# io-ol2.net
KiCad netlist of a schematic drawn in EAGLE
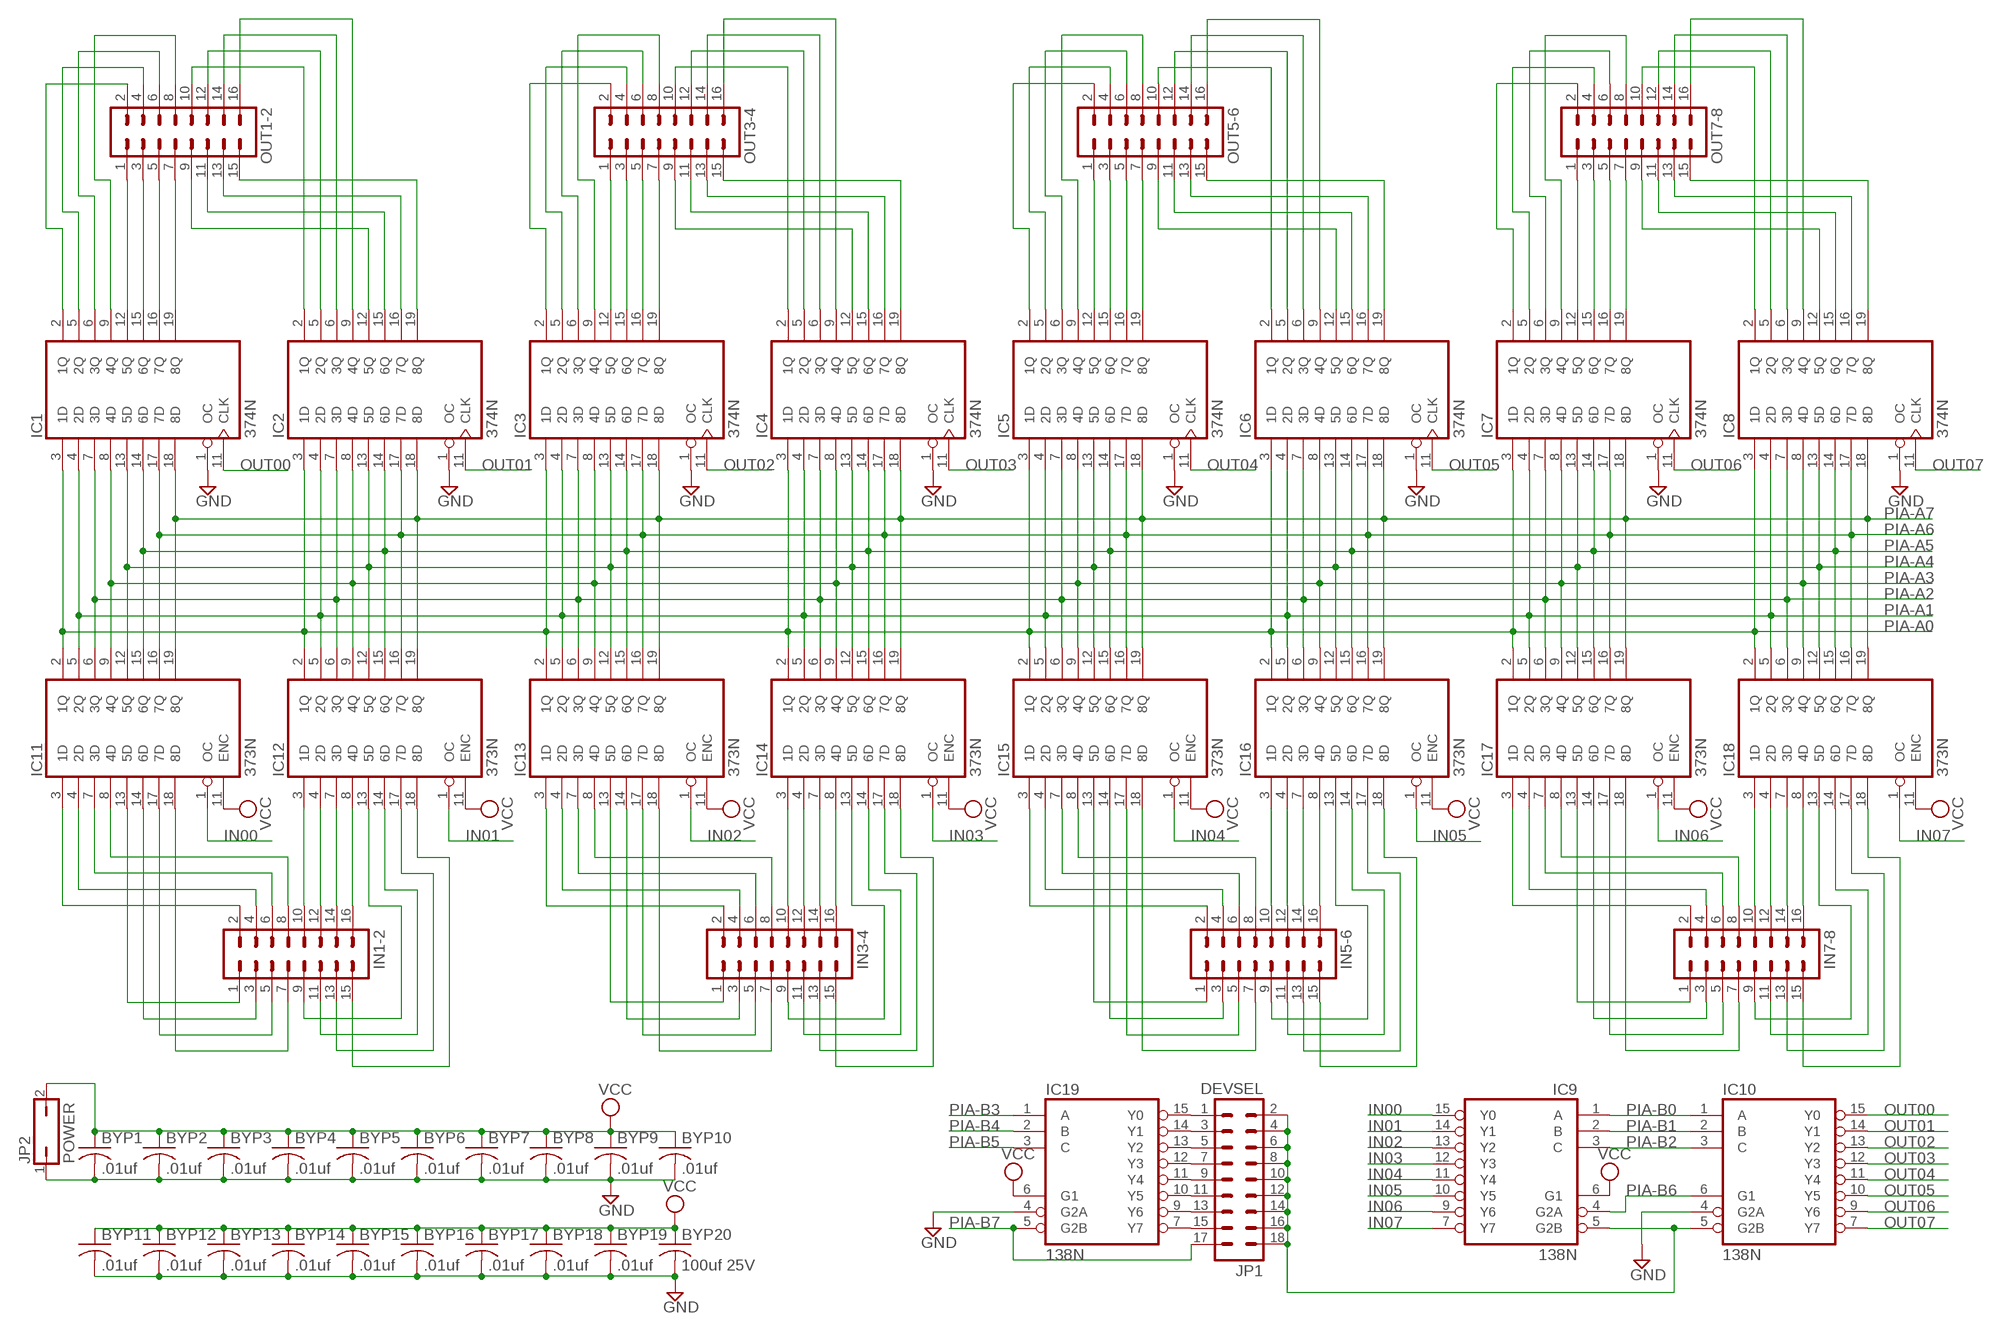
[diagram p0: schematic, sheet 1]
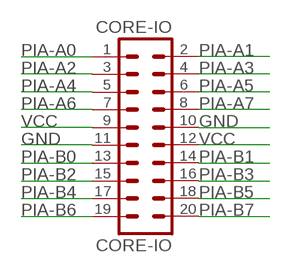
[diagram p1: schematic, sheet 2]

(export (version "E")
  (design (tool "Eeschema 10.0.6"))
  (components
    (comp (ref "BYP1")
      (value ".01uf")
      (footprint "eagle-import:C050-025X075")
      (libsource (lib "eagle-import") (part "C-US050-025X075"))
    )
    (comp (ref "BYP2")
      (value ".01uf")
      (footprint "eagle-import:C050-025X075")
      (libsource (lib "eagle-import") (part "C-US050-025X075"))
    )
    (comp (ref "BYP3")
      (value ".01uf")
      (footprint "eagle-import:C050-025X075")
      (libsource (lib "eagle-import") (part "C-US050-025X075"))
    )
    (comp (ref "BYP4")
      (value ".01uf")
      (footprint "eagle-import:C050-025X075")
      (libsource (lib "eagle-import") (part "C-US050-025X075"))
    )
    (comp (ref "BYP5")
      (value ".01uf")
      (footprint "eagle-import:C050-025X075")
      (libsource (lib "eagle-import") (part "C-US050-025X075"))
    )
    (comp (ref "BYP6")
      (value ".01uf")
      (footprint "eagle-import:C050-025X075")
      (libsource (lib "eagle-import") (part "C-US050-025X075"))
    )
    (comp (ref "BYP7")
      (value ".01uf")
      (footprint "eagle-import:C050-025X075")
      (libsource (lib "eagle-import") (part "C-US050-025X075"))
    )
    (comp (ref "BYP8")
      (value ".01uf")
      (footprint "eagle-import:C050-025X075")
      (libsource (lib "eagle-import") (part "C-US050-025X075"))
    )
    (comp (ref "BYP9")
      (value ".01uf")
      (footprint "eagle-import:C050-025X075")
      (libsource (lib "eagle-import") (part "C-US050-025X075"))
    )
    (comp (ref "BYP10")
      (value ".01uf")
      (footprint "eagle-import:C050-025X075")
      (libsource (lib "eagle-import") (part "C-US050-025X075"))
    )
    (comp (ref "BYP11")
      (value ".01uf")
      (footprint "eagle-import:C050-025X075")
      (libsource (lib "eagle-import") (part "C-US050-025X075"))
    )
    (comp (ref "BYP12")
      (value ".01uf")
      (footprint "eagle-import:C050-025X075")
      (libsource (lib "eagle-import") (part "C-US050-025X075"))
    )
    (comp (ref "BYP13")
      (value ".01uf")
      (footprint "eagle-import:C050-025X075")
      (libsource (lib "eagle-import") (part "C-US050-025X075"))
    )
    (comp (ref "BYP14")
      (value ".01uf")
      (footprint "eagle-import:C050-025X075")
      (libsource (lib "eagle-import") (part "C-US050-025X075"))
    )
    (comp (ref "BYP15")
      (value ".01uf")
      (footprint "eagle-import:C050-025X075")
      (libsource (lib "eagle-import") (part "C-US050-025X075"))
    )
    (comp (ref "BYP16")
      (value ".01uf")
      (footprint "eagle-import:C050-025X075")
      (libsource (lib "eagle-import") (part "C-US050-025X075"))
    )
    (comp (ref "BYP17")
      (value ".01uf")
      (footprint "eagle-import:C050-025X075")
      (libsource (lib "eagle-import") (part "C-US050-025X075"))
    )
    (comp (ref "BYP18")
      (value ".01uf")
      (footprint "eagle-import:C050-025X075")
      (libsource (lib "eagle-import") (part "C-US050-025X075"))
    )
    (comp (ref "BYP19")
      (value ".01uf")
      (footprint "eagle-import:C050-025X075")
      (libsource (lib "eagle-import") (part "C-US050-025X075"))
    )
    (comp (ref "BYP20")
      (value "100uf 25V")
      (footprint "eagle-import:C150-064X183")
      (libsource (lib "eagle-import") (part "C-US150-064X183"))
    )
    (comp (ref "IC1")
      (value "374N")
      (footprint "eagle-import:DIL20")
      (libsource (lib "eagle-import") (part "74374NLS"))
    )
    (comp (ref "IC2")
      (value "374N")
      (footprint "eagle-import:DIL20")
      (libsource (lib "eagle-import") (part "74374NLS"))
    )
    (comp (ref "IC3")
      (value "374N")
      (footprint "eagle-import:DIL20")
      (libsource (lib "eagle-import") (part "74374NLS"))
    )
    (comp (ref "IC4")
      (value "374N")
      (footprint "eagle-import:DIL20")
      (libsource (lib "eagle-import") (part "74374NLS"))
    )
    (comp (ref "IC5")
      (value "374N")
      (footprint "eagle-import:DIL20")
      (libsource (lib "eagle-import") (part "74374NLS"))
    )
    (comp (ref "IC6")
      (value "374N")
      (footprint "eagle-import:DIL20")
      (libsource (lib "eagle-import") (part "74374NLS"))
    )
    (comp (ref "IC7")
      (value "374N")
      (footprint "eagle-import:DIL20")
      (libsource (lib "eagle-import") (part "74374NLS"))
    )
    (comp (ref "IC8")
      (value "374N")
      (footprint "eagle-import:DIL20")
      (libsource (lib "eagle-import") (part "74374NLS"))
    )
    (comp (ref "IC9")
      (value "138N")
      (footprint "eagle-import:DIL16")
      (libsource (lib "eagle-import") (part "74138NLS"))
    )
    (comp (ref "IC10")
      (value "138N")
      (footprint "eagle-import:DIL16")
      (libsource (lib "eagle-import") (part "74138NLS"))
    )
    (comp (ref "IC11")
      (value "373N")
      (footprint "eagle-import:DIL20")
      (libsource (lib "eagle-import") (part "74373NLS"))
    )
    (comp (ref "IC12")
      (value "373N")
      (footprint "eagle-import:DIL20")
      (libsource (lib "eagle-import") (part "74373NLS"))
    )
    (comp (ref "IC13")
      (value "373N")
      (footprint "eagle-import:DIL20")
      (libsource (lib "eagle-import") (part "74373NLS"))
    )
    (comp (ref "IC14")
      (value "373N")
      (footprint "eagle-import:DIL20")
      (libsource (lib "eagle-import") (part "74373NLS"))
    )
    (comp (ref "IC15")
      (value "373N")
      (footprint "eagle-import:DIL20")
      (libsource (lib "eagle-import") (part "74373NLS"))
    )
    (comp (ref "IC16")
      (value "373N")
      (footprint "eagle-import:DIL20")
      (libsource (lib "eagle-import") (part "74373NLS"))
    )
    (comp (ref "IC17")
      (value "373N")
      (footprint "eagle-import:DIL20")
      (libsource (lib "eagle-import") (part "74373NLS"))
    )
    (comp (ref "IC18")
      (value "373N")
      (footprint "eagle-import:DIL20")
      (libsource (lib "eagle-import") (part "74373NLS"))
    )
    (comp (ref "IC19")
      (value "138N")
      (footprint "eagle-import:DIL16")
      (libsource (lib "eagle-import") (part "74138NLS"))
    )
    (comp (ref "IN1-2")
      (value "MA08-2")
      (footprint "eagle-import:MA08-2")
      (libsource (lib "eagle-import") (part "MA08-2"))
    )
    (comp (ref "IN3-4")
      (value "MA08-2")
      (footprint "eagle-import:MA08-2")
      (libsource (lib "eagle-import") (part "MA08-2"))
    )
    (comp (ref "IN5-6")
      (value "MA08-2")
      (footprint "eagle-import:MA08-2")
      (libsource (lib "eagle-import") (part "MA08-2"))
    )
    (comp (ref "IN7-8")
      (value "MA08-2")
      (footprint "eagle-import:MA08-2")
      (libsource (lib "eagle-import") (part "MA08-2"))
    )
    (comp (ref "JP1")
      (value "DEVSEL")
      (footprint "eagle-import:MA09-2")
      (libsource (lib "eagle-import") (part "MA09-2"))
    )
    (comp (ref "JP2")
      (value "POWER")
      (footprint "eagle-import:JP1")
      (libsource (lib "eagle-import") (part "JP1Q"))
    )
    (comp (ref "OUT1-2")
      (value "MA08-2")
      (footprint "eagle-import:MA08-2")
      (libsource (lib "eagle-import") (part "MA08-2"))
    )
    (comp (ref "OUT3-4")
      (value "MA08-2")
      (footprint "eagle-import:MA08-2")
      (libsource (lib "eagle-import") (part "MA08-2"))
    )
    (comp (ref "OUT5-6")
      (value "MA08-2")
      (footprint "eagle-import:MA08-2")
      (libsource (lib "eagle-import") (part "MA08-2"))
    )
    (comp (ref "OUT7-8")
      (value "MA08-2")
      (footprint "eagle-import:MA08-2")
      (libsource (lib "eagle-import") (part "MA08-2"))
    )
    (comp (ref "CORE-IO")
      (value "CORE-IO")
      (footprint "eagle-import:MA10-2")
      (libsource (lib "eagle-import") (part "MA10-2"))
    )
  )
  (nets
    (net (code "1") (name "GND") (class "Default")
      (node (ref "BYP1") (pin "2") (pinfunction "2_2") (pintype "passive"))
      (node (ref "BYP10") (pin "2") (pinfunction "2_2") (pintype "passive"))
      (node (ref "BYP11") (pin "2") (pinfunction "2_2") (pintype "passive"))
      (node (ref "BYP12") (pin "2") (pinfunction "2_2") (pintype "passive"))
      (node (ref "BYP13") (pin "2") (pinfunction "2_2") (pintype "passive"))
      (node (ref "BYP14") (pin "2") (pinfunction "2_2") (pintype "passive"))
      (node (ref "BYP15") (pin "2") (pinfunction "2_2") (pintype "passive"))
      (node (ref "BYP16") (pin "2") (pinfunction "2_2") (pintype "passive"))
      (node (ref "BYP17") (pin "2") (pinfunction "2_2") (pintype "passive"))
      (node (ref "BYP18") (pin "2") (pinfunction "2_2") (pintype "passive"))
      (node (ref "BYP19") (pin "2") (pinfunction "2_2") (pintype "passive"))
      (node (ref "BYP2") (pin "2") (pinfunction "2_2") (pintype "passive"))
      (node (ref "BYP20") (pin "2") (pinfunction "2_2") (pintype "passive"))
      (node (ref "BYP3") (pin "2") (pinfunction "2_2") (pintype "passive"))
      (node (ref "BYP4") (pin "2") (pinfunction "2_2") (pintype "passive"))
      (node (ref "BYP5") (pin "2") (pinfunction "2_2") (pintype "passive"))
      (node (ref "BYP6") (pin "2") (pinfunction "2_2") (pintype "passive"))
      (node (ref "BYP7") (pin "2") (pinfunction "2_2") (pintype "passive"))
      (node (ref "BYP8") (pin "2") (pinfunction "2_2") (pintype "passive"))
      (node (ref "BYP9") (pin "2") (pinfunction "2_2") (pintype "passive"))
      (node (ref "CORE-IO") (pin "10") (pinfunction "10_10") (pintype "passive"))
      (node (ref "CORE-IO") (pin "11") (pinfunction "11_11") (pintype "passive"))
      (node (ref "IC1") (pin "1") (pinfunction "OC_1") (pintype "input"))
      (node (ref "IC10") (pin "4") (pinfunction "G2A_4") (pintype "input"))
      (node (ref "IC19") (pin "4") (pinfunction "G2A_4") (pintype "input"))
      (node (ref "IC2") (pin "1") (pinfunction "OC_1") (pintype "input"))
      (node (ref "IC3") (pin "1") (pinfunction "OC_1") (pintype "input"))
      (node (ref "IC4") (pin "1") (pinfunction "OC_1") (pintype "input"))
      (node (ref "IC5") (pin "1") (pinfunction "OC_1") (pintype "input"))
      (node (ref "IC6") (pin "1") (pinfunction "OC_1") (pintype "input"))
      (node (ref "IC7") (pin "1") (pinfunction "OC_1") (pintype "input"))
      (node (ref "IC8") (pin "1") (pinfunction "OC_1") (pintype "input"))
      (node (ref "JP2") (pin "1") (pinfunction "1_1") (pintype "passive"))
    )
    (net (code "2") (name "IN00") (class "Default")
      (node (ref "IC11") (pin "1") (pinfunction "OC_1") (pintype "input"))
      (node (ref "IC9") (pin "15") (pinfunction "Y0_15") (pintype "output"))
    )
    (net (code "3") (name "IN01") (class "Default")
      (node (ref "IC12") (pin "1") (pinfunction "OC_1") (pintype "input"))
      (node (ref "IC9") (pin "14") (pinfunction "Y1_14") (pintype "output"))
    )
    (net (code "4") (name "IN02") (class "Default")
      (node (ref "IC13") (pin "1") (pinfunction "OC_1") (pintype "input"))
      (node (ref "IC9") (pin "13") (pinfunction "Y2_13") (pintype "output"))
    )
    (net (code "5") (name "IN03") (class "Default")
      (node (ref "IC14") (pin "1") (pinfunction "OC_1") (pintype "input"))
      (node (ref "IC9") (pin "12") (pinfunction "Y3_12") (pintype "output"))
    )
    (net (code "6") (name "IN04") (class "Default")
      (node (ref "IC15") (pin "1") (pinfunction "OC_1") (pintype "input"))
      (node (ref "IC9") (pin "11") (pinfunction "Y4_11") (pintype "output"))
    )
    (net (code "7") (name "IN05") (class "Default")
      (node (ref "IC16") (pin "1") (pinfunction "OC_1") (pintype "input"))
      (node (ref "IC9") (pin "10") (pinfunction "Y5_10") (pintype "output"))
    )
    (net (code "8") (name "IN06") (class "Default")
      (node (ref "IC17") (pin "1") (pinfunction "OC_1") (pintype "input"))
      (node (ref "IC9") (pin "9") (pinfunction "Y6_9") (pintype "output"))
    )
    (net (code "9") (name "IN07") (class "Default")
      (node (ref "IC18") (pin "1") (pinfunction "OC_1") (pintype "input"))
      (node (ref "IC9") (pin "7") (pinfunction "Y7_7") (pintype "output"))
    )
    (net (code "10") (name "Net-(IC1A-1Q)") (class "Default")
      (node (ref "IC1") (pin "2") (pinfunction "1Q_2") (pintype "tri_state"))
      (node (ref "OUT1-2") (pin "2") (pinfunction "2_2") (pintype "passive"))
    )
    (net (code "11") (name "Net-(IC1A-2Q)") (class "Default")
      (node (ref "IC1") (pin "5") (pinfunction "2Q_5") (pintype "tri_state"))
      (node (ref "OUT1-2") (pin "4") (pinfunction "4_4") (pintype "passive"))
    )
    (net (code "12") (name "Net-(IC1A-3Q)") (class "Default")
      (node (ref "IC1") (pin "6") (pinfunction "3Q_6") (pintype "tri_state"))
      (node (ref "OUT1-2") (pin "6") (pinfunction "6_6") (pintype "passive"))
    )
    (net (code "13") (name "Net-(IC1A-4Q)") (class "Default")
      (node (ref "IC1") (pin "9") (pinfunction "4Q_9") (pintype "tri_state"))
      (node (ref "OUT1-2") (pin "8") (pinfunction "8_8") (pintype "passive"))
    )
    (net (code "14") (name "Net-(IC1A-5Q)") (class "Default")
      (node (ref "IC1") (pin "12") (pinfunction "5Q_12") (pintype "tri_state"))
      (node (ref "OUT1-2") (pin "1") (pinfunction "1_1") (pintype "passive"))
    )
    (net (code "15") (name "Net-(IC1A-6Q)") (class "Default")
      (node (ref "IC1") (pin "15") (pinfunction "6Q_15") (pintype "tri_state"))
      (node (ref "OUT1-2") (pin "3") (pinfunction "3_3") (pintype "passive"))
    )
    (net (code "16") (name "Net-(IC1A-7Q)") (class "Default")
      (node (ref "IC1") (pin "16") (pinfunction "7Q_16") (pintype "tri_state"))
      (node (ref "OUT1-2") (pin "5") (pinfunction "5_5") (pintype "passive"))
    )
    (net (code "17") (name "Net-(IC1A-8Q)") (class "Default")
      (node (ref "IC1") (pin "19") (pinfunction "8Q_19") (pintype "tri_state"))
      (node (ref "OUT1-2") (pin "7") (pinfunction "7_7") (pintype "passive"))
    )
    (net (code "18") (name "Net-(IC2A-1Q)") (class "Default")
      (node (ref "IC2") (pin "2") (pinfunction "1Q_2") (pintype "tri_state"))
      (node (ref "OUT1-2") (pin "10") (pinfunction "10_10") (pintype "passive"))
    )
    (net (code "19") (name "Net-(IC2A-2Q)") (class "Default")
      (node (ref "IC2") (pin "5") (pinfunction "2Q_5") (pintype "tri_state"))
      (node (ref "OUT1-2") (pin "12") (pinfunction "12_12") (pintype "passive"))
    )
    (net (code "20") (name "Net-(IC2A-3Q)") (class "Default")
      (node (ref "IC2") (pin "6") (pinfunction "3Q_6") (pintype "tri_state"))
      (node (ref "OUT1-2") (pin "14") (pinfunction "14_14") (pintype "passive"))
    )
    (net (code "21") (name "Net-(IC2A-4Q)") (class "Default")
      (node (ref "IC2") (pin "9") (pinfunction "4Q_9") (pintype "tri_state"))
      (node (ref "OUT1-2") (pin "16") (pinfunction "16_16") (pintype "passive"))
    )
    (net (code "22") (name "Net-(IC2A-5Q)") (class "Default")
      (node (ref "IC2") (pin "12") (pinfunction "5Q_12") (pintype "tri_state"))
      (node (ref "OUT1-2") (pin "9") (pinfunction "9_9") (pintype "passive"))
    )
    (net (code "23") (name "Net-(IC2A-6Q)") (class "Default")
      (node (ref "IC2") (pin "15") (pinfunction "6Q_15") (pintype "tri_state"))
      (node (ref "OUT1-2") (pin "11") (pinfunction "11_11") (pintype "passive"))
    )
    (net (code "24") (name "Net-(IC2A-7Q)") (class "Default")
      (node (ref "IC2") (pin "16") (pinfunction "7Q_16") (pintype "tri_state"))
      (node (ref "OUT1-2") (pin "13") (pinfunction "13_13") (pintype "passive"))
    )
    (net (code "25") (name "Net-(IC2A-8Q)") (class "Default")
      (node (ref "IC2") (pin "19") (pinfunction "8Q_19") (pintype "tri_state"))
      (node (ref "OUT1-2") (pin "15") (pinfunction "15_15") (pintype "passive"))
    )
    (net (code "26") (name "Net-(IC3A-1Q)") (class "Default")
      (node (ref "IC3") (pin "2") (pinfunction "1Q_2") (pintype "tri_state"))
      (node (ref "OUT3-4") (pin "2") (pinfunction "2_2") (pintype "passive"))
    )
    (net (code "27") (name "Net-(IC3A-2Q)") (class "Default")
      (node (ref "IC3") (pin "5") (pinfunction "2Q_5") (pintype "tri_state"))
      (node (ref "OUT3-4") (pin "4") (pinfunction "4_4") (pintype "passive"))
    )
    (net (code "28") (name "Net-(IC3A-3Q)") (class "Default")
      (node (ref "IC3") (pin "6") (pinfunction "3Q_6") (pintype "tri_state"))
      (node (ref "OUT3-4") (pin "6") (pinfunction "6_6") (pintype "passive"))
    )
    (net (code "29") (name "Net-(IC3A-4Q)") (class "Default")
      (node (ref "IC3") (pin "9") (pinfunction "4Q_9") (pintype "tri_state"))
      (node (ref "OUT3-4") (pin "8") (pinfunction "8_8") (pintype "passive"))
    )
    (net (code "30") (name "Net-(IC3A-5Q)") (class "Default")
      (node (ref "IC3") (pin "12") (pinfunction "5Q_12") (pintype "tri_state"))
      (node (ref "OUT3-4") (pin "1") (pinfunction "1_1") (pintype "passive"))
    )
    (net (code "31") (name "Net-(IC3A-6Q)") (class "Default")
      (node (ref "IC3") (pin "15") (pinfunction "6Q_15") (pintype "tri_state"))
      (node (ref "OUT3-4") (pin "3") (pinfunction "3_3") (pintype "passive"))
    )
    (net (code "32") (name "Net-(IC3A-7Q)") (class "Default")
      (node (ref "IC3") (pin "16") (pinfunction "7Q_16") (pintype "tri_state"))
      (node (ref "OUT3-4") (pin "5") (pinfunction "5_5") (pintype "passive"))
    )
    (net (code "33") (name "Net-(IC3A-8Q)") (class "Default")
      (node (ref "IC3") (pin "19") (pinfunction "8Q_19") (pintype "tri_state"))
      (node (ref "OUT3-4") (pin "7") (pinfunction "7_7") (pintype "passive"))
    )
    (net (code "34") (name "Net-(IC4A-1Q)") (class "Default")
      (node (ref "IC4") (pin "2") (pinfunction "1Q_2") (pintype "tri_state"))
      (node (ref "OUT3-4") (pin "10") (pinfunction "10_10") (pintype "passive"))
    )
    (net (code "35") (name "Net-(IC4A-2Q)") (class "Default")
      (node (ref "IC4") (pin "5") (pinfunction "2Q_5") (pintype "tri_state"))
      (node (ref "OUT3-4") (pin "12") (pinfunction "12_12") (pintype "passive"))
    )
    (net (code "36") (name "Net-(IC4A-3Q)") (class "Default")
      (node (ref "IC4") (pin "6") (pinfunction "3Q_6") (pintype "tri_state"))
      (node (ref "OUT3-4") (pin "14") (pinfunction "14_14") (pintype "passive"))
    )
    (net (code "37") (name "Net-(IC4A-4Q)") (class "Default")
      (node (ref "IC4") (pin "9") (pinfunction "4Q_9") (pintype "tri_state"))
      (node (ref "OUT3-4") (pin "16") (pinfunction "16_16") (pintype "passive"))
    )
    (net (code "38") (name "Net-(IC4A-5Q)") (class "Default")
      (node (ref "IC4") (pin "12") (pinfunction "5Q_12") (pintype "tri_state"))
      (node (ref "OUT3-4") (pin "9") (pinfunction "9_9") (pintype "passive"))
    )
    (net (code "39") (name "Net-(IC4A-6Q)") (class "Default")
      (node (ref "IC4") (pin "15") (pinfunction "6Q_15") (pintype "tri_state"))
      (node (ref "OUT3-4") (pin "11") (pinfunction "11_11") (pintype "passive"))
    )
    (net (code "40") (name "Net-(IC4A-7Q)") (class "Default")
      (node (ref "IC4") (pin "16") (pinfunction "7Q_16") (pintype "tri_state"))
      (node (ref "OUT3-4") (pin "13") (pinfunction "13_13") (pintype "passive"))
    )
    (net (code "41") (name "Net-(IC4A-8Q)") (class "Default")
      (node (ref "IC4") (pin "19") (pinfunction "8Q_19") (pintype "tri_state"))
      (node (ref "OUT3-4") (pin "15") (pinfunction "15_15") (pintype "passive"))
    )
    (net (code "42") (name "Net-(IC5A-1Q)") (class "Default")
      (node (ref "IC5") (pin "2") (pinfunction "1Q_2") (pintype "tri_state"))
      (node (ref "OUT5-6") (pin "2") (pinfunction "2_2") (pintype "passive"))
    )
    (net (code "43") (name "Net-(IC5A-2Q)") (class "Default")
      (node (ref "IC5") (pin "5") (pinfunction "2Q_5") (pintype "tri_state"))
      (node (ref "OUT5-6") (pin "4") (pinfunction "4_4") (pintype "passive"))
    )
    (net (code "44") (name "Net-(IC5A-3Q)") (class "Default")
      (node (ref "IC5") (pin "6") (pinfunction "3Q_6") (pintype "tri_state"))
      (node (ref "OUT5-6") (pin "6") (pinfunction "6_6") (pintype "passive"))
    )
    (net (code "45") (name "Net-(IC5A-4Q)") (class "Default")
      (node (ref "IC5") (pin "9") (pinfunction "4Q_9") (pintype "tri_state"))
      (node (ref "OUT5-6") (pin "8") (pinfunction "8_8") (pintype "passive"))
    )
    (net (code "46") (name "Net-(IC5A-5Q)") (class "Default")
      (node (ref "IC5") (pin "12") (pinfunction "5Q_12") (pintype "tri_state"))
      (node (ref "OUT5-6") (pin "1") (pinfunction "1_1") (pintype "passive"))
    )
    (net (code "47") (name "Net-(IC5A-6Q)") (class "Default")
      (node (ref "IC5") (pin "15") (pinfunction "6Q_15") (pintype "tri_state"))
      (node (ref "OUT5-6") (pin "3") (pinfunction "3_3") (pintype "passive"))
    )
    (net (code "48") (name "Net-(IC5A-7Q)") (class "Default")
      (node (ref "IC5") (pin "16") (pinfunction "7Q_16") (pintype "tri_state"))
      (node (ref "OUT5-6") (pin "5") (pinfunction "5_5") (pintype "passive"))
    )
    (net (code "49") (name "Net-(IC5A-8Q)") (class "Default")
      (node (ref "IC5") (pin "19") (pinfunction "8Q_19") (pintype "tri_state"))
      (node (ref "OUT5-6") (pin "7") (pinfunction "7_7") (pintype "passive"))
    )
    (net (code "50") (name "Net-(IC6A-1Q)") (class "Default")
      (node (ref "IC6") (pin "2") (pinfunction "1Q_2") (pintype "tri_state"))
      (node (ref "OUT5-6") (pin "10") (pinfunction "10_10") (pintype "passive"))
    )
    (net (code "51") (name "Net-(IC6A-2Q)") (class "Default")
      (node (ref "IC6") (pin "5") (pinfunction "2Q_5") (pintype "tri_state"))
      (node (ref "OUT5-6") (pin "12") (pinfunction "12_12") (pintype "passive"))
    )
    (net (code "52") (name "Net-(IC6A-3Q)") (class "Default")
      (node (ref "IC6") (pin "6") (pinfunction "3Q_6") (pintype "tri_state"))
      (node (ref "OUT5-6") (pin "14") (pinfunction "14_14") (pintype "passive"))
    )
    (net (code "53") (name "Net-(IC6A-4Q)") (class "Default")
      (node (ref "IC6") (pin "9") (pinfunction "4Q_9") (pintype "tri_state"))
      (node (ref "OUT5-6") (pin "16") (pinfunction "16_16") (pintype "passive"))
    )
    (net (code "54") (name "Net-(IC6A-5Q)") (class "Default")
      (node (ref "IC6") (pin "12") (pinfunction "5Q_12") (pintype "tri_state"))
      (node (ref "OUT5-6") (pin "9") (pinfunction "9_9") (pintype "passive"))
    )
    (net (code "55") (name "Net-(IC6A-6Q)") (class "Default")
      (node (ref "IC6") (pin "15") (pinfunction "6Q_15") (pintype "tri_state"))
      (node (ref "OUT5-6") (pin "11") (pinfunction "11_11") (pintype "passive"))
    )
    (net (code "56") (name "Net-(IC6A-7Q)") (class "Default")
      (node (ref "IC6") (pin "16") (pinfunction "7Q_16") (pintype "tri_state"))
      (node (ref "OUT5-6") (pin "13") (pinfunction "13_13") (pintype "passive"))
    )
    (net (code "57") (name "Net-(IC6A-8Q)") (class "Default")
      (node (ref "IC6") (pin "19") (pinfunction "8Q_19") (pintype "tri_state"))
      (node (ref "OUT5-6") (pin "15") (pinfunction "15_15") (pintype "passive"))
    )
    (net (code "58") (name "Net-(IC7A-1Q)") (class "Default")
      (node (ref "IC7") (pin "2") (pinfunction "1Q_2") (pintype "tri_state"))
      (node (ref "OUT7-8") (pin "2") (pinfunction "2_2") (pintype "passive"))
    )
    (net (code "59") (name "Net-(IC7A-2Q)") (class "Default")
      (node (ref "IC7") (pin "5") (pinfunction "2Q_5") (pintype "tri_state"))
      (node (ref "OUT7-8") (pin "4") (pinfunction "4_4") (pintype "passive"))
    )
    (net (code "60") (name "Net-(IC7A-3Q)") (class "Default")
      (node (ref "IC7") (pin "6") (pinfunction "3Q_6") (pintype "tri_state"))
      (node (ref "OUT7-8") (pin "6") (pinfunction "6_6") (pintype "passive"))
    )
    (net (code "61") (name "Net-(IC7A-4Q)") (class "Default")
      (node (ref "IC7") (pin "9") (pinfunction "4Q_9") (pintype "tri_state"))
      (node (ref "OUT7-8") (pin "8") (pinfunction "8_8") (pintype "passive"))
    )
    (net (code "62") (name "Net-(IC7A-5Q)") (class "Default")
      (node (ref "IC7") (pin "12") (pinfunction "5Q_12") (pintype "tri_state"))
      (node (ref "OUT7-8") (pin "1") (pinfunction "1_1") (pintype "passive"))
    )
    (net (code "63") (name "Net-(IC7A-6Q)") (class "Default")
      (node (ref "IC7") (pin "15") (pinfunction "6Q_15") (pintype "tri_state"))
      (node (ref "OUT7-8") (pin "3") (pinfunction "3_3") (pintype "passive"))
    )
    (net (code "64") (name "Net-(IC7A-7Q)") (class "Default")
      (node (ref "IC7") (pin "16") (pinfunction "7Q_16") (pintype "tri_state"))
      (node (ref "OUT7-8") (pin "5") (pinfunction "5_5") (pintype "passive"))
    )
    (net (code "65") (name "Net-(IC7A-8Q)") (class "Default")
      (node (ref "IC7") (pin "19") (pinfunction "8Q_19") (pintype "tri_state"))
      (node (ref "OUT7-8") (pin "7") (pinfunction "7_7") (pintype "passive"))
    )
    (net (code "66") (name "Net-(IC8A-1Q)") (class "Default")
      (node (ref "IC8") (pin "2") (pinfunction "1Q_2") (pintype "tri_state"))
      (node (ref "OUT7-8") (pin "10") (pinfunction "10_10") (pintype "passive"))
    )
    (net (code "67") (name "Net-(IC8A-2Q)") (class "Default")
      (node (ref "IC8") (pin "5") (pinfunction "2Q_5") (pintype "tri_state"))
      (node (ref "OUT7-8") (pin "12") (pinfunction "12_12") (pintype "passive"))
    )
    (net (code "68") (name "Net-(IC8A-3Q)") (class "Default")
      (node (ref "IC8") (pin "6") (pinfunction "3Q_6") (pintype "tri_state"))
      (node (ref "OUT7-8") (pin "14") (pinfunction "14_14") (pintype "passive"))
    )
    (net (code "69") (name "Net-(IC8A-4Q)") (class "Default")
      (node (ref "IC8") (pin "9") (pinfunction "4Q_9") (pintype "tri_state"))
      (node (ref "OUT7-8") (pin "16") (pinfunction "16_16") (pintype "passive"))
    )
    (net (code "70") (name "Net-(IC8A-5Q)") (class "Default")
      (node (ref "IC8") (pin "12") (pinfunction "5Q_12") (pintype "tri_state"))
      (node (ref "OUT7-8") (pin "9") (pinfunction "9_9") (pintype "passive"))
    )
    (net (code "71") (name "Net-(IC8A-6Q)") (class "Default")
      (node (ref "IC8") (pin "15") (pinfunction "6Q_15") (pintype "tri_state"))
      (node (ref "OUT7-8") (pin "11") (pinfunction "11_11") (pintype "passive"))
    )
    (net (code "72") (name "Net-(IC8A-7Q)") (class "Default")
      (node (ref "IC8") (pin "16") (pinfunction "7Q_16") (pintype "tri_state"))
      (node (ref "OUT7-8") (pin "13") (pinfunction "13_13") (pintype "passive"))
    )
    (net (code "73") (name "Net-(IC8A-8Q)") (class "Default")
      (node (ref "IC8") (pin "19") (pinfunction "8Q_19") (pintype "tri_state"))
      (node (ref "OUT7-8") (pin "15") (pinfunction "15_15") (pintype "passive"))
    )
    (net (code "74") (name "Net-(IC10A-G2B)") (class "Default")
      (node (ref "IC10") (pin "5") (pinfunction "G2B_5") (pintype "input"))
      (node (ref "IC9") (pin "5") (pinfunction "G2B_5") (pintype "input"))
      (node (ref "JP1") (pin "10") (pinfunction "10_10") (pintype "passive"))
      (node (ref "JP1") (pin "12") (pinfunction "12_12") (pintype "passive"))
      (node (ref "JP1") (pin "14") (pinfunction "14_14") (pintype "passive"))
      (node (ref "JP1") (pin "16") (pinfunction "16_16") (pintype "passive"))
      (node (ref "JP1") (pin "18") (pinfunction "18_18") (pintype "passive"))
      (node (ref "JP1") (pin "2") (pinfunction "2_2") (pintype "passive"))
      (node (ref "JP1") (pin "4") (pinfunction "4_4") (pintype "passive"))
      (node (ref "JP1") (pin "6") (pinfunction "6_6") (pintype "passive"))
      (node (ref "JP1") (pin "8") (pinfunction "8_8") (pintype "passive"))
    )
    (net (code "75") (name "Net-(IC11A-1D)") (class "Default")
      (node (ref "IC11") (pin "3") (pinfunction "1D_3") (pintype "input"))
      (node (ref "IN1-2") (pin "2") (pinfunction "2_2") (pintype "passive"))
    )
    (net (code "76") (name "Net-(IC11A-2D)") (class "Default")
      (node (ref "IC11") (pin "4") (pinfunction "2D_4") (pintype "input"))
      (node (ref "IN1-2") (pin "4") (pinfunction "4_4") (pintype "passive"))
    )
    (net (code "77") (name "Net-(IC11A-3D)") (class "Default")
      (node (ref "IC11") (pin "7") (pinfunction "3D_7") (pintype "input"))
      (node (ref "IN1-2") (pin "6") (pinfunction "6_6") (pintype "passive"))
    )
    (net (code "78") (name "Net-(IC11A-4D)") (class "Default")
      (node (ref "IC11") (pin "8") (pinfunction "4D_8") (pintype "input"))
      (node (ref "IN1-2") (pin "8") (pinfunction "8_8") (pintype "passive"))
    )
    (net (code "79") (name "Net-(IC11A-5D)") (class "Default")
      (node (ref "IC11") (pin "13") (pinfunction "5D_13") (pintype "input"))
      (node (ref "IN1-2") (pin "1") (pinfunction "1_1") (pintype "passive"))
    )
    (net (code "80") (name "Net-(IC11A-6D)") (class "Default")
      (node (ref "IC11") (pin "14") (pinfunction "6D_14") (pintype "input"))
      (node (ref "IN1-2") (pin "3") (pinfunction "3_3") (pintype "passive"))
    )
    (net (code "81") (name "Net-(IC11A-7D)") (class "Default")
      (node (ref "IC11") (pin "17") (pinfunction "7D_17") (pintype "input"))
      (node (ref "IN1-2") (pin "5") (pinfunction "5_5") (pintype "passive"))
    )
    (net (code "82") (name "Net-(IC11A-8D)") (class "Default")
      (node (ref "IC11") (pin "18") (pinfunction "8D_18") (pintype "input"))
      (node (ref "IN1-2") (pin "7") (pinfunction "7_7") (pintype "passive"))
    )
    (net (code "83") (name "Net-(IC12A-1D)") (class "Default")
      (node (ref "IC12") (pin "3") (pinfunction "1D_3") (pintype "input"))
      (node (ref "IN1-2") (pin "10") (pinfunction "10_10") (pintype "passive"))
    )
    (net (code "84") (name "Net-(IC12A-2D)") (class "Default")
      (node (ref "IC12") (pin "4") (pinfunction "2D_4") (pintype "input"))
      (node (ref "IN1-2") (pin "12") (pinfunction "12_12") (pintype "passive"))
    )
    (net (code "85") (name "Net-(IC12A-3D)") (class "Default")
      (node (ref "IC12") (pin "7") (pinfunction "3D_7") (pintype "input"))
      (node (ref "IN1-2") (pin "14") (pinfunction "14_14") (pintype "passive"))
    )
    (net (code "86") (name "Net-(IC12A-4D)") (class "Default")
      (node (ref "IC12") (pin "8") (pinfunction "4D_8") (pintype "input"))
      (node (ref "IN1-2") (pin "16") (pinfunction "16_16") (pintype "passive"))
    )
    (net (code "87") (name "Net-(IC12A-5D)") (class "Default")
      (node (ref "IC12") (pin "13") (pinfunction "5D_13") (pintype "input"))
      (node (ref "IN1-2") (pin "9") (pinfunction "9_9") (pintype "passive"))
    )
    (net (code "88") (name "Net-(IC12A-6D)") (class "Default")
      (node (ref "IC12") (pin "14") (pinfunction "6D_14") (pintype "input"))
      (node (ref "IN1-2") (pin "11") (pinfunction "11_11") (pintype "passive"))
    )
    (net (code "89") (name "Net-(IC12A-7D)") (class "Default")
      (node (ref "IC12") (pin "17") (pinfunction "7D_17") (pintype "input"))
      (node (ref "IN1-2") (pin "13") (pinfunction "13_13") (pintype "passive"))
    )
    (net (code "90") (name "Net-(IC12A-8D)") (class "Default")
      (node (ref "IC12") (pin "18") (pinfunction "8D_18") (pintype "input"))
      (node (ref "IN1-2") (pin "15") (pinfunction "15_15") (pintype "passive"))
    )
    (net (code "91") (name "Net-(IC13A-1D)") (class "Default")
      (node (ref "IC13") (pin "3") (pinfunction "1D_3") (pintype "input"))
      (node (ref "IN3-4") (pin "2") (pinfunction "2_2") (pintype "passive"))
    )
    (net (code "92") (name "Net-(IC13A-2D)") (class "Default")
      (node (ref "IC13") (pin "4") (pinfunction "2D_4") (pintype "input"))
      (node (ref "IN3-4") (pin "4") (pinfunction "4_4") (pintype "passive"))
    )
    (net (code "93") (name "Net-(IC13A-3D)") (class "Default")
      (node (ref "IC13") (pin "7") (pinfunction "3D_7") (pintype "input"))
      (node (ref "IN3-4") (pin "6") (pinfunction "6_6") (pintype "passive"))
    )
    (net (code "94") (name "Net-(IC13A-4D)") (class "Default")
      (node (ref "IC13") (pin "8") (pinfunction "4D_8") (pintype "input"))
      (node (ref "IN3-4") (pin "8") (pinfunction "8_8") (pintype "passive"))
    )
    (net (code "95") (name "Net-(IC13A-5D)") (class "Default")
      (node (ref "IC13") (pin "13") (pinfunction "5D_13") (pintype "input"))
      (node (ref "IN3-4") (pin "1") (pinfunction "1_1") (pintype "passive"))
    )
    (net (code "96") (name "Net-(IC13A-6D)") (class "Default")
      (node (ref "IC13") (pin "14") (pinfunction "6D_14") (pintype "input"))
      (node (ref "IN3-4") (pin "3") (pinfunction "3_3") (pintype "passive"))
    )
    (net (code "97") (name "Net-(IC13A-7D)") (class "Default")
      (node (ref "IC13") (pin "17") (pinfunction "7D_17") (pintype "input"))
      (node (ref "IN3-4") (pin "5") (pinfunction "5_5") (pintype "passive"))
    )
    (net (code "98") (name "Net-(IC13A-8D)") (class "Default")
      (node (ref "IC13") (pin "18") (pinfunction "8D_18") (pintype "input"))
      (node (ref "IN3-4") (pin "7") (pinfunction "7_7") (pintype "passive"))
    )
    (net (code "99") (name "Net-(IC14A-1D)") (class "Default")
      (node (ref "IC14") (pin "3") (pinfunction "1D_3") (pintype "input"))
      (node (ref "IN3-4") (pin "10") (pinfunction "10_10") (pintype "passive"))
    )
    (net (code "100") (name "Net-(IC14A-2D)") (class "Default")
      (node (ref "IC14") (pin "4") (pinfunction "2D_4") (pintype "input"))
      (node (ref "IN3-4") (pin "12") (pinfunction "12_12") (pintype "passive"))
    )
    (net (code "101") (name "Net-(IC14A-3D)") (class "Default")
      (node (ref "IC14") (pin "7") (pinfunction "3D_7") (pintype "input"))
      (node (ref "IN3-4") (pin "14") (pinfunction "14_14") (pintype "passive"))
    )
    (net (code "102") (name "Net-(IC14A-4D)") (class "Default")
      (node (ref "IC14") (pin "8") (pinfunction "4D_8") (pintype "input"))
      (node (ref "IN3-4") (pin "16") (pinfunction "16_16") (pintype "passive"))
    )
    (net (code "103") (name "Net-(IC14A-5D)") (class "Default")
      (node (ref "IC14") (pin "13") (pinfunction "5D_13") (pintype "input"))
      (node (ref "IN3-4") (pin "9") (pinfunction "9_9") (pintype "passive"))
    )
    (net (code "104") (name "Net-(IC14A-6D)") (class "Default")
      (node (ref "IC14") (pin "14") (pinfunction "6D_14") (pintype "input"))
      (node (ref "IN3-4") (pin "11") (pinfunction "11_11") (pintype "passive"))
    )
    (net (code "105") (name "Net-(IC14A-7D)") (class "Default")
      (node (ref "IC14") (pin "17") (pinfunction "7D_17") (pintype "input"))
      (node (ref "IN3-4") (pin "13") (pinfunction "13_13") (pintype "passive"))
    )
    (net (code "106") (name "Net-(IC14A-8D)") (class "Default")
      (node (ref "IC14") (pin "18") (pinfunction "8D_18") (pintype "input"))
      (node (ref "IN3-4") (pin "15") (pinfunction "15_15") (pintype "passive"))
    )
    (net (code "107") (name "Net-(IC15A-1D)") (class "Default")
      (node (ref "IC15") (pin "3") (pinfunction "1D_3") (pintype "input"))
      (node (ref "IN5-6") (pin "2") (pinfunction "2_2") (pintype "passive"))
    )
    (net (code "108") (name "Net-(IC15A-2D)") (class "Default")
      (node (ref "IC15") (pin "4") (pinfunction "2D_4") (pintype "input"))
      (node (ref "IN5-6") (pin "4") (pinfunction "4_4") (pintype "passive"))
    )
    (net (code "109") (name "Net-(IC15A-3D)") (class "Default")
      (node (ref "IC15") (pin "7") (pinfunction "3D_7") (pintype "input"))
      (node (ref "IN5-6") (pin "6") (pinfunction "6_6") (pintype "passive"))
    )
    (net (code "110") (name "Net-(IC15A-4D)") (class "Default")
      (node (ref "IC15") (pin "8") (pinfunction "4D_8") (pintype "input"))
      (node (ref "IN5-6") (pin "8") (pinfunction "8_8") (pintype "passive"))
    )
    (net (code "111") (name "Net-(IC15A-5D)") (class "Default")
      (node (ref "IC15") (pin "13") (pinfunction "5D_13") (pintype "input"))
      (node (ref "IN5-6") (pin "1") (pinfunction "1_1") (pintype "passive"))
    )
    (net (code "112") (name "Net-(IC15A-6D)") (class "Default")
      (node (ref "IC15") (pin "14") (pinfunction "6D_14") (pintype "input"))
      (node (ref "IN5-6") (pin "3") (pinfunction "3_3") (pintype "passive"))
    )
    (net (code "113") (name "Net-(IC15A-7D)") (class "Default")
      (node (ref "IC15") (pin "17") (pinfunction "7D_17") (pintype "input"))
      (node (ref "IN5-6") (pin "5") (pinfunction "5_5") (pintype "passive"))
    )
    (net (code "114") (name "Net-(IC15A-8D)") (class "Default")
      (node (ref "IC15") (pin "18") (pinfunction "8D_18") (pintype "input"))
      (node (ref "IN5-6") (pin "7") (pinfunction "7_7") (pintype "passive"))
    )
    (net (code "115") (name "Net-(IC16A-1D)") (class "Default")
      (node (ref "IC16") (pin "3") (pinfunction "1D_3") (pintype "input"))
      (node (ref "IN5-6") (pin "10") (pinfunction "10_10") (pintype "passive"))
    )
    (net (code "116") (name "Net-(IC16A-2D)") (class "Default")
      (node (ref "IC16") (pin "4") (pinfunction "2D_4") (pintype "input"))
      (node (ref "IN5-6") (pin "12") (pinfunction "12_12") (pintype "passive"))
    )
    (net (code "117") (name "Net-(IC16A-3D)") (class "Default")
      (node (ref "IC16") (pin "7") (pinfunction "3D_7") (pintype "input"))
      (node (ref "IN5-6") (pin "14") (pinfunction "14_14") (pintype "passive"))
    )
    (net (code "118") (name "Net-(IC16A-4D)") (class "Default")
      (node (ref "IC16") (pin "8") (pinfunction "4D_8") (pintype "input"))
      (node (ref "IN5-6") (pin "16") (pinfunction "16_16") (pintype "passive"))
    )
    (net (code "119") (name "Net-(IC16A-5D)") (class "Default")
      (node (ref "IC16") (pin "13") (pinfunction "5D_13") (pintype "input"))
      (node (ref "IN5-6") (pin "9") (pinfunction "9_9") (pintype "passive"))
    )
    (net (code "120") (name "Net-(IC16A-6D)") (class "Default")
      (node (ref "IC16") (pin "14") (pinfunction "6D_14") (pintype "input"))
      (node (ref "IN5-6") (pin "11") (pinfunction "11_11") (pintype "passive"))
    )
    (net (code "121") (name "Net-(IC16A-7D)") (class "Default")
      (node (ref "IC16") (pin "17") (pinfunction "7D_17") (pintype "input"))
      (node (ref "IN5-6") (pin "13") (pinfunction "13_13") (pintype "passive"))
    )
    (net (code "122") (name "Net-(IC16A-8D)") (class "Default")
      (node (ref "IC16") (pin "18") (pinfunction "8D_18") (pintype "input"))
      (node (ref "IN5-6") (pin "15") (pinfunction "15_15") (pintype "passive"))
    )
    (net (code "123") (name "Net-(IC17A-1D)") (class "Default")
      (node (ref "IC17") (pin "3") (pinfunction "1D_3") (pintype "input"))
      (node (ref "IN7-8") (pin "2") (pinfunction "2_2") (pintype "passive"))
    )
    (net (code "124") (name "Net-(IC17A-2D)") (class "Default")
      (node (ref "IC17") (pin "4") (pinfunction "2D_4") (pintype "input"))
      (node (ref "IN7-8") (pin "4") (pinfunction "4_4") (pintype "passive"))
    )
    (net (code "125") (name "Net-(IC17A-3D)") (class "Default")
      (node (ref "IC17") (pin "7") (pinfunction "3D_7") (pintype "input"))
      (node (ref "IN7-8") (pin "6") (pinfunction "6_6") (pintype "passive"))
    )
    (net (code "126") (name "Net-(IC17A-4D)") (class "Default")
      (node (ref "IC17") (pin "8") (pinfunction "4D_8") (pintype "input"))
      (node (ref "IN7-8") (pin "8") (pinfunction "8_8") (pintype "passive"))
    )
    (net (code "127") (name "Net-(IC17A-5D)") (class "Default")
      (node (ref "IC17") (pin "13") (pinfunction "5D_13") (pintype "input"))
      (node (ref "IN7-8") (pin "1") (pinfunction "1_1") (pintype "passive"))
    )
    (net (code "128") (name "Net-(IC17A-6D)") (class "Default")
      (node (ref "IC17") (pin "14") (pinfunction "6D_14") (pintype "input"))
      (node (ref "IN7-8") (pin "3") (pinfunction "3_3") (pintype "passive"))
    )
    (net (code "129") (name "Net-(IC17A-7D)") (class "Default")
      (node (ref "IC17") (pin "17") (pinfunction "7D_17") (pintype "input"))
      (node (ref "IN7-8") (pin "5") (pinfunction "5_5") (pintype "passive"))
    )
    (net (code "130") (name "Net-(IC17A-8D)") (class "Default")
      (node (ref "IC17") (pin "18") (pinfunction "8D_18") (pintype "input"))
      (node (ref "IN7-8") (pin "7") (pinfunction "7_7") (pintype "passive"))
    )
    (net (code "131") (name "Net-(IC18A-1D)") (class "Default")
      (node (ref "IC18") (pin "3") (pinfunction "1D_3") (pintype "input"))
      (node (ref "IN7-8") (pin "10") (pinfunction "10_10") (pintype "passive"))
    )
    (net (code "132") (name "Net-(IC18A-2D)") (class "Default")
      (node (ref "IC18") (pin "4") (pinfunction "2D_4") (pintype "input"))
      (node (ref "IN7-8") (pin "12") (pinfunction "12_12") (pintype "passive"))
    )
    (net (code "133") (name "Net-(IC18A-3D)") (class "Default")
      (node (ref "IC18") (pin "7") (pinfunction "3D_7") (pintype "input"))
      (node (ref "IN7-8") (pin "14") (pinfunction "14_14") (pintype "passive"))
    )
    (net (code "134") (name "Net-(IC18A-4D)") (class "Default")
      (node (ref "IC18") (pin "8") (pinfunction "4D_8") (pintype "input"))
      (node (ref "IN7-8") (pin "16") (pinfunction "16_16") (pintype "passive"))
    )
    (net (code "135") (name "Net-(IC18A-5D)") (class "Default")
      (node (ref "IC18") (pin "13") (pinfunction "5D_13") (pintype "input"))
      (node (ref "IN7-8") (pin "9") (pinfunction "9_9") (pintype "passive"))
    )
    (net (code "136") (name "Net-(IC18A-6D)") (class "Default")
      (node (ref "IC18") (pin "14") (pinfunction "6D_14") (pintype "input"))
      (node (ref "IN7-8") (pin "11") (pinfunction "11_11") (pintype "passive"))
    )
    (net (code "137") (name "Net-(IC18A-7D)") (class "Default")
      (node (ref "IC18") (pin "17") (pinfunction "7D_17") (pintype "input"))
      (node (ref "IN7-8") (pin "13") (pinfunction "13_13") (pintype "passive"))
    )
    (net (code "138") (name "Net-(IC18A-8D)") (class "Default")
      (node (ref "IC18") (pin "18") (pinfunction "8D_18") (pintype "input"))
      (node (ref "IN7-8") (pin "15") (pinfunction "15_15") (pintype "passive"))
    )
    (net (code "139") (name "Net-(IC19A-Y0)") (class "Default")
      (node (ref "IC19") (pin "15") (pinfunction "Y0_15") (pintype "output"))
      (node (ref "JP1") (pin "1") (pinfunction "1_1") (pintype "passive"))
    )
    (net (code "140") (name "Net-(IC19A-Y1)") (class "Default")
      (node (ref "IC19") (pin "14") (pinfunction "Y1_14") (pintype "output"))
      (node (ref "JP1") (pin "3") (pinfunction "3_3") (pintype "passive"))
    )
    (net (code "141") (name "Net-(IC19A-Y2)") (class "Default")
      (node (ref "IC19") (pin "13") (pinfunction "Y2_13") (pintype "output"))
      (node (ref "JP1") (pin "5") (pinfunction "5_5") (pintype "passive"))
    )
    (net (code "142") (name "Net-(IC19A-Y3)") (class "Default")
      (node (ref "IC19") (pin "12") (pinfunction "Y3_12") (pintype "output"))
      (node (ref "JP1") (pin "7") (pinfunction "7_7") (pintype "passive"))
    )
    (net (code "143") (name "Net-(IC19A-Y4)") (class "Default")
      (node (ref "IC19") (pin "11") (pinfunction "Y4_11") (pintype "output"))
      (node (ref "JP1") (pin "9") (pinfunction "9_9") (pintype "passive"))
    )
    (net (code "144") (name "Net-(IC19A-Y5)") (class "Default")
      (node (ref "IC19") (pin "10") (pinfunction "Y5_10") (pintype "output"))
      (node (ref "JP1") (pin "11") (pinfunction "11_11") (pintype "passive"))
    )
    (net (code "145") (name "Net-(IC19A-Y6)") (class "Default")
      (node (ref "IC19") (pin "9") (pinfunction "Y6_9") (pintype "output"))
      (node (ref "JP1") (pin "13") (pinfunction "13_13") (pintype "passive"))
    )
    (net (code "146") (name "Net-(IC19A-Y7)") (class "Default")
      (node (ref "IC19") (pin "7") (pinfunction "Y7_7") (pintype "output"))
      (node (ref "JP1") (pin "15") (pinfunction "15_15") (pintype "passive"))
    )
    (net (code "147") (name "OUT00") (class "Default")
      (node (ref "IC1") (pin "11") (pinfunction "CLK_11") (pintype "input"))
      (node (ref "IC10") (pin "15") (pinfunction "Y0_15") (pintype "output"))
    )
    (net (code "148") (name "OUT01") (class "Default")
      (node (ref "IC10") (pin "14") (pinfunction "Y1_14") (pintype "output"))
      (node (ref "IC2") (pin "11") (pinfunction "CLK_11") (pintype "input"))
    )
    (net (code "149") (name "OUT02") (class "Default")
      (node (ref "IC10") (pin "13") (pinfunction "Y2_13") (pintype "output"))
      (node (ref "IC3") (pin "11") (pinfunction "CLK_11") (pintype "input"))
    )
    (net (code "150") (name "OUT03") (class "Default")
      (node (ref "IC10") (pin "12") (pinfunction "Y3_12") (pintype "output"))
      (node (ref "IC4") (pin "11") (pinfunction "CLK_11") (pintype "input"))
    )
    (net (code "151") (name "OUT04") (class "Default")
      (node (ref "IC10") (pin "11") (pinfunction "Y4_11") (pintype "output"))
      (node (ref "IC5") (pin "11") (pinfunction "CLK_11") (pintype "input"))
    )
    (net (code "152") (name "OUT05") (class "Default")
      (node (ref "IC10") (pin "10") (pinfunction "Y5_10") (pintype "output"))
      (node (ref "IC6") (pin "11") (pinfunction "CLK_11") (pintype "input"))
    )
    (net (code "153") (name "OUT06") (class "Default")
      (node (ref "IC10") (pin "9") (pinfunction "Y6_9") (pintype "output"))
      (node (ref "IC7") (pin "11") (pinfunction "CLK_11") (pintype "input"))
    )
    (net (code "154") (name "OUT07") (class "Default")
      (node (ref "IC10") (pin "7") (pinfunction "Y7_7") (pintype "output"))
      (node (ref "IC8") (pin "11") (pinfunction "CLK_11") (pintype "input"))
    )
    (net (code "155") (name "PIA-A0") (class "Default")
      (node (ref "CORE-IO") (pin "1") (pinfunction "1_1") (pintype "passive"))
      (node (ref "IC1") (pin "3") (pinfunction "1D_3") (pintype "input"))
      (node (ref "IC11") (pin "2") (pinfunction "1Q_2") (pintype "tri_state"))
      (node (ref "IC12") (pin "2") (pinfunction "1Q_2") (pintype "tri_state"))
      (node (ref "IC13") (pin "2") (pinfunction "1Q_2") (pintype "tri_state"))
      (node (ref "IC14") (pin "2") (pinfunction "1Q_2") (pintype "tri_state"))
      (node (ref "IC15") (pin "2") (pinfunction "1Q_2") (pintype "tri_state"))
      (node (ref "IC16") (pin "2") (pinfunction "1Q_2") (pintype "tri_state"))
      (node (ref "IC17") (pin "2") (pinfunction "1Q_2") (pintype "tri_state"))
      (node (ref "IC18") (pin "2") (pinfunction "1Q_2") (pintype "tri_state"))
      (node (ref "IC2") (pin "3") (pinfunction "1D_3") (pintype "input"))
      (node (ref "IC3") (pin "3") (pinfunction "1D_3") (pintype "input"))
      (node (ref "IC4") (pin "3") (pinfunction "1D_3") (pintype "input"))
      (node (ref "IC5") (pin "3") (pinfunction "1D_3") (pintype "input"))
      (node (ref "IC6") (pin "3") (pinfunction "1D_3") (pintype "input"))
      (node (ref "IC7") (pin "3") (pinfunction "1D_3") (pintype "input"))
      (node (ref "IC8") (pin "3") (pinfunction "1D_3") (pintype "input"))
    )
    (net (code "156") (name "PIA-A1") (class "Default")
      (node (ref "CORE-IO") (pin "2") (pinfunction "2_2") (pintype "passive"))
      (node (ref "IC1") (pin "4") (pinfunction "2D_4") (pintype "input"))
      (node (ref "IC11") (pin "5") (pinfunction "2Q_5") (pintype "tri_state"))
      (node (ref "IC12") (pin "5") (pinfunction "2Q_5") (pintype "tri_state"))
      (node (ref "IC13") (pin "5") (pinfunction "2Q_5") (pintype "tri_state"))
      (node (ref "IC14") (pin "5") (pinfunction "2Q_5") (pintype "tri_state"))
      (node (ref "IC15") (pin "5") (pinfunction "2Q_5") (pintype "tri_state"))
      (node (ref "IC16") (pin "5") (pinfunction "2Q_5") (pintype "tri_state"))
      (node (ref "IC17") (pin "5") (pinfunction "2Q_5") (pintype "tri_state"))
      (node (ref "IC18") (pin "5") (pinfunction "2Q_5") (pintype "tri_state"))
      (node (ref "IC2") (pin "4") (pinfunction "2D_4") (pintype "input"))
      (node (ref "IC3") (pin "4") (pinfunction "2D_4") (pintype "input"))
      (node (ref "IC4") (pin "4") (pinfunction "2D_4") (pintype "input"))
      (node (ref "IC5") (pin "4") (pinfunction "2D_4") (pintype "input"))
      (node (ref "IC6") (pin "4") (pinfunction "2D_4") (pintype "input"))
      (node (ref "IC7") (pin "4") (pinfunction "2D_4") (pintype "input"))
      (node (ref "IC8") (pin "4") (pinfunction "2D_4") (pintype "input"))
    )
    (net (code "157") (name "PIA-A2") (class "Default")
      (node (ref "CORE-IO") (pin "3") (pinfunction "3_3") (pintype "passive"))
      (node (ref "IC1") (pin "7") (pinfunction "3D_7") (pintype "input"))
      (node (ref "IC11") (pin "6") (pinfunction "3Q_6") (pintype "tri_state"))
      (node (ref "IC12") (pin "6") (pinfunction "3Q_6") (pintype "tri_state"))
      (node (ref "IC13") (pin "6") (pinfunction "3Q_6") (pintype "tri_state"))
      (node (ref "IC14") (pin "6") (pinfunction "3Q_6") (pintype "tri_state"))
      (node (ref "IC15") (pin "6") (pinfunction "3Q_6") (pintype "tri_state"))
      (node (ref "IC16") (pin "6") (pinfunction "3Q_6") (pintype "tri_state"))
      (node (ref "IC17") (pin "6") (pinfunction "3Q_6") (pintype "tri_state"))
      (node (ref "IC18") (pin "6") (pinfunction "3Q_6") (pintype "tri_state"))
      (node (ref "IC2") (pin "7") (pinfunction "3D_7") (pintype "input"))
      (node (ref "IC3") (pin "7") (pinfunction "3D_7") (pintype "input"))
      (node (ref "IC4") (pin "7") (pinfunction "3D_7") (pintype "input"))
      (node (ref "IC5") (pin "7") (pinfunction "3D_7") (pintype "input"))
      (node (ref "IC6") (pin "7") (pinfunction "3D_7") (pintype "input"))
      (node (ref "IC7") (pin "7") (pinfunction "3D_7") (pintype "input"))
      (node (ref "IC8") (pin "7") (pinfunction "3D_7") (pintype "input"))
    )
    (net (code "158") (name "PIA-A3") (class "Default")
      (node (ref "CORE-IO") (pin "4") (pinfunction "4_4") (pintype "passive"))
      (node (ref "IC1") (pin "8") (pinfunction "4D_8") (pintype "input"))
      (node (ref "IC11") (pin "9") (pinfunction "4Q_9") (pintype "tri_state"))
      (node (ref "IC12") (pin "9") (pinfunction "4Q_9") (pintype "tri_state"))
      (node (ref "IC13") (pin "9") (pinfunction "4Q_9") (pintype "tri_state"))
      (node (ref "IC14") (pin "9") (pinfunction "4Q_9") (pintype "tri_state"))
      (node (ref "IC15") (pin "9") (pinfunction "4Q_9") (pintype "tri_state"))
      (node (ref "IC16") (pin "9") (pinfunction "4Q_9") (pintype "tri_state"))
      (node (ref "IC17") (pin "9") (pinfunction "4Q_9") (pintype "tri_state"))
      (node (ref "IC18") (pin "9") (pinfunction "4Q_9") (pintype "tri_state"))
      (node (ref "IC2") (pin "8") (pinfunction "4D_8") (pintype "input"))
      (node (ref "IC3") (pin "8") (pinfunction "4D_8") (pintype "input"))
      (node (ref "IC4") (pin "8") (pinfunction "4D_8") (pintype "input"))
      (node (ref "IC5") (pin "8") (pinfunction "4D_8") (pintype "input"))
      (node (ref "IC6") (pin "8") (pinfunction "4D_8") (pintype "input"))
      (node (ref "IC7") (pin "8") (pinfunction "4D_8") (pintype "input"))
      (node (ref "IC8") (pin "8") (pinfunction "4D_8") (pintype "input"))
    )
    (net (code "159") (name "PIA-A4") (class "Default")
      (node (ref "CORE-IO") (pin "5") (pinfunction "5_5") (pintype "passive"))
      (node (ref "IC1") (pin "13") (pinfunction "5D_13") (pintype "input"))
      (node (ref "IC11") (pin "12") (pinfunction "5Q_12") (pintype "tri_state"))
      (node (ref "IC12") (pin "12") (pinfunction "5Q_12") (pintype "tri_state"))
      (node (ref "IC13") (pin "12") (pinfunction "5Q_12") (pintype "tri_state"))
      (node (ref "IC14") (pin "12") (pinfunction "5Q_12") (pintype "tri_state"))
      (node (ref "IC15") (pin "12") (pinfunction "5Q_12") (pintype "tri_state"))
      (node (ref "IC16") (pin "12") (pinfunction "5Q_12") (pintype "tri_state"))
      (node (ref "IC17") (pin "12") (pinfunction "5Q_12") (pintype "tri_state"))
      (node (ref "IC18") (pin "12") (pinfunction "5Q_12") (pintype "tri_state"))
      (node (ref "IC2") (pin "13") (pinfunction "5D_13") (pintype "input"))
      (node (ref "IC3") (pin "13") (pinfunction "5D_13") (pintype "input"))
      (node (ref "IC4") (pin "13") (pinfunction "5D_13") (pintype "input"))
      (node (ref "IC5") (pin "13") (pinfunction "5D_13") (pintype "input"))
      (node (ref "IC6") (pin "13") (pinfunction "5D_13") (pintype "input"))
      (node (ref "IC7") (pin "13") (pinfunction "5D_13") (pintype "input"))
      (node (ref "IC8") (pin "13") (pinfunction "5D_13") (pintype "input"))
    )
    (net (code "160") (name "PIA-A5") (class "Default")
      (node (ref "CORE-IO") (pin "6") (pinfunction "6_6") (pintype "passive"))
      (node (ref "IC1") (pin "14") (pinfunction "6D_14") (pintype "input"))
      (node (ref "IC11") (pin "15") (pinfunction "6Q_15") (pintype "tri_state"))
      (node (ref "IC12") (pin "15") (pinfunction "6Q_15") (pintype "tri_state"))
      (node (ref "IC13") (pin "15") (pinfunction "6Q_15") (pintype "tri_state"))
      (node (ref "IC14") (pin "15") (pinfunction "6Q_15") (pintype "tri_state"))
      (node (ref "IC15") (pin "15") (pinfunction "6Q_15") (pintype "tri_state"))
      (node (ref "IC16") (pin "15") (pinfunction "6Q_15") (pintype "tri_state"))
      (node (ref "IC17") (pin "15") (pinfunction "6Q_15") (pintype "tri_state"))
      (node (ref "IC18") (pin "15") (pinfunction "6Q_15") (pintype "tri_state"))
      (node (ref "IC2") (pin "14") (pinfunction "6D_14") (pintype "input"))
      (node (ref "IC3") (pin "14") (pinfunction "6D_14") (pintype "input"))
      (node (ref "IC4") (pin "14") (pinfunction "6D_14") (pintype "input"))
      (node (ref "IC5") (pin "14") (pinfunction "6D_14") (pintype "input"))
      (node (ref "IC6") (pin "14") (pinfunction "6D_14") (pintype "input"))
      (node (ref "IC7") (pin "14") (pinfunction "6D_14") (pintype "input"))
      (node (ref "IC8") (pin "14") (pinfunction "6D_14") (pintype "input"))
    )
    (net (code "161") (name "PIA-A6") (class "Default")
      (node (ref "CORE-IO") (pin "7") (pinfunction "7_7") (pintype "passive"))
      (node (ref "IC1") (pin "17") (pinfunction "7D_17") (pintype "input"))
      (node (ref "IC11") (pin "16") (pinfunction "7Q_16") (pintype "tri_state"))
      (node (ref "IC12") (pin "16") (pinfunction "7Q_16") (pintype "tri_state"))
      (node (ref "IC13") (pin "16") (pinfunction "7Q_16") (pintype "tri_state"))
      (node (ref "IC14") (pin "16") (pinfunction "7Q_16") (pintype "tri_state"))
      (node (ref "IC15") (pin "16") (pinfunction "7Q_16") (pintype "tri_state"))
      (node (ref "IC16") (pin "16") (pinfunction "7Q_16") (pintype "tri_state"))
      (node (ref "IC17") (pin "16") (pinfunction "7Q_16") (pintype "tri_state"))
      (node (ref "IC18") (pin "16") (pinfunction "7Q_16") (pintype "tri_state"))
      (node (ref "IC2") (pin "17") (pinfunction "7D_17") (pintype "input"))
      (node (ref "IC3") (pin "17") (pinfunction "7D_17") (pintype "input"))
      (node (ref "IC4") (pin "17") (pinfunction "7D_17") (pintype "input"))
      (node (ref "IC5") (pin "17") (pinfunction "7D_17") (pintype "input"))
      (node (ref "IC6") (pin "17") (pinfunction "7D_17") (pintype "input"))
      (node (ref "IC7") (pin "17") (pinfunction "7D_17") (pintype "input"))
      (node (ref "IC8") (pin "17") (pinfunction "7D_17") (pintype "input"))
    )
    (net (code "162") (name "PIA-A7") (class "Default")
      (node (ref "CORE-IO") (pin "8") (pinfunction "8_8") (pintype "passive"))
      (node (ref "IC1") (pin "18") (pinfunction "8D_18") (pintype "input"))
      (node (ref "IC11") (pin "19") (pinfunction "8Q_19") (pintype "tri_state"))
      (node (ref "IC12") (pin "19") (pinfunction "8Q_19") (pintype "tri_state"))
      (node (ref "IC13") (pin "19") (pinfunction "8Q_19") (pintype "tri_state"))
      (node (ref "IC14") (pin "19") (pinfunction "8Q_19") (pintype "tri_state"))
      (node (ref "IC15") (pin "19") (pinfunction "8Q_19") (pintype "tri_state"))
      (node (ref "IC16") (pin "19") (pinfunction "8Q_19") (pintype "tri_state"))
      (node (ref "IC17") (pin "19") (pinfunction "8Q_19") (pintype "tri_state"))
      (node (ref "IC18") (pin "19") (pinfunction "8Q_19") (pintype "tri_state"))
      (node (ref "IC2") (pin "18") (pinfunction "8D_18") (pintype "input"))
      (node (ref "IC3") (pin "18") (pinfunction "8D_18") (pintype "input"))
      (node (ref "IC4") (pin "18") (pinfunction "8D_18") (pintype "input"))
      (node (ref "IC5") (pin "18") (pinfunction "8D_18") (pintype "input"))
      (node (ref "IC6") (pin "18") (pinfunction "8D_18") (pintype "input"))
      (node (ref "IC7") (pin "18") (pinfunction "8D_18") (pintype "input"))
      (node (ref "IC8") (pin "18") (pinfunction "8D_18") (pintype "input"))
    )
    (net (code "163") (name "PIA-B0") (class "Default")
      (node (ref "CORE-IO") (pin "13") (pinfunction "13_13") (pintype "passive"))
      (node (ref "IC10") (pin "1") (pinfunction "A_1") (pintype "input"))
      (node (ref "IC9") (pin "1") (pinfunction "A_1") (pintype "input"))
    )
    (net (code "164") (name "PIA-B1") (class "Default")
      (node (ref "CORE-IO") (pin "14") (pinfunction "14_14") (pintype "passive"))
      (node (ref "IC10") (pin "2") (pinfunction "B_2") (pintype "input"))
      (node (ref "IC9") (pin "2") (pinfunction "B_2") (pintype "input"))
    )
    (net (code "165") (name "PIA-B2") (class "Default")
      (node (ref "CORE-IO") (pin "15") (pinfunction "15_15") (pintype "passive"))
      (node (ref "IC10") (pin "3") (pinfunction "C_3") (pintype "input"))
      (node (ref "IC9") (pin "3") (pinfunction "C_3") (pintype "input"))
    )
    (net (code "166") (name "PIA-B3") (class "Default")
      (node (ref "CORE-IO") (pin "16") (pinfunction "16_16") (pintype "passive"))
      (node (ref "IC19") (pin "1") (pinfunction "A_1") (pintype "input"))
    )
    (net (code "167") (name "PIA-B4") (class "Default")
      (node (ref "CORE-IO") (pin "17") (pinfunction "17_17") (pintype "passive"))
      (node (ref "IC19") (pin "2") (pinfunction "B_2") (pintype "input"))
    )
    (net (code "168") (name "PIA-B5") (class "Default")
      (node (ref "CORE-IO") (pin "18") (pinfunction "18_18") (pintype "passive"))
      (node (ref "IC19") (pin "3") (pinfunction "C_3") (pintype "input"))
    )
    (net (code "169") (name "PIA-B6") (class "Default")
      (node (ref "CORE-IO") (pin "19") (pinfunction "19_19") (pintype "passive"))
      (node (ref "IC10") (pin "6") (pinfunction "G1_6") (pintype "input"))
      (node (ref "IC9") (pin "4") (pinfunction "G2A_4") (pintype "input"))
    )
    (net (code "170") (name "PIA-B7") (class "Default")
      (node (ref "CORE-IO") (pin "20") (pinfunction "20_20") (pintype "passive"))
      (node (ref "IC19") (pin "5") (pinfunction "G2B_5") (pintype "input"))
      (node (ref "JP1") (pin "17") (pinfunction "17_17") (pintype "passive"))
    )
    (net (code "171") (name "VCC") (class "Default")
      (node (ref "BYP1") (pin "1") (pinfunction "1_1") (pintype "passive"))
      (node (ref "BYP10") (pin "1") (pinfunction "1_1") (pintype "passive"))
      (node (ref "BYP11") (pin "1") (pinfunction "1_1") (pintype "passive"))
      (node (ref "BYP12") (pin "1") (pinfunction "1_1") (pintype "passive"))
      (node (ref "BYP13") (pin "1") (pinfunction "1_1") (pintype "passive"))
      (node (ref "BYP14") (pin "1") (pinfunction "1_1") (pintype "passive"))
      (node (ref "BYP15") (pin "1") (pinfunction "1_1") (pintype "passive"))
      (node (ref "BYP16") (pin "1") (pinfunction "1_1") (pintype "passive"))
      (node (ref "BYP17") (pin "1") (pinfunction "1_1") (pintype "passive"))
      (node (ref "BYP18") (pin "1") (pinfunction "1_1") (pintype "passive"))
      (node (ref "BYP19") (pin "1") (pinfunction "1_1") (pintype "passive"))
      (node (ref "BYP2") (pin "1") (pinfunction "1_1") (pintype "passive"))
      (node (ref "BYP20") (pin "1") (pinfunction "1_1") (pintype "passive"))
      (node (ref "BYP3") (pin "1") (pinfunction "1_1") (pintype "passive"))
      (node (ref "BYP4") (pin "1") (pinfunction "1_1") (pintype "passive"))
      (node (ref "BYP5") (pin "1") (pinfunction "1_1") (pintype "passive"))
      (node (ref "BYP6") (pin "1") (pinfunction "1_1") (pintype "passive"))
      (node (ref "BYP7") (pin "1") (pinfunction "1_1") (pintype "passive"))
      (node (ref "BYP8") (pin "1") (pinfunction "1_1") (pintype "passive"))
      (node (ref "BYP9") (pin "1") (pinfunction "1_1") (pintype "passive"))
      (node (ref "CORE-IO") (pin "12") (pinfunction "12_12") (pintype "passive"))
      (node (ref "CORE-IO") (pin "9") (pinfunction "9_9") (pintype "passive"))
      (node (ref "IC11") (pin "11") (pinfunction "ENC_11") (pintype "input"))
      (node (ref "IC12") (pin "11") (pinfunction "ENC_11") (pintype "input"))
      (node (ref "IC13") (pin "11") (pinfunction "ENC_11") (pintype "input"))
      (node (ref "IC14") (pin "11") (pinfunction "ENC_11") (pintype "input"))
      (node (ref "IC15") (pin "11") (pinfunction "ENC_11") (pintype "input"))
      (node (ref "IC16") (pin "11") (pinfunction "ENC_11") (pintype "input"))
      (node (ref "IC17") (pin "11") (pinfunction "ENC_11") (pintype "input"))
      (node (ref "IC18") (pin "11") (pinfunction "ENC_11") (pintype "input"))
      (node (ref "IC19") (pin "6") (pinfunction "G1_6") (pintype "input"))
      (node (ref "IC9") (pin "6") (pinfunction "G1_6") (pintype "input"))
      (node (ref "JP2") (pin "2") (pinfunction "2_2") (pintype "passive"))
    )
  )
)
